# Power_Supply.net
KiCad netlist of a schematic drawn in Altium Designer
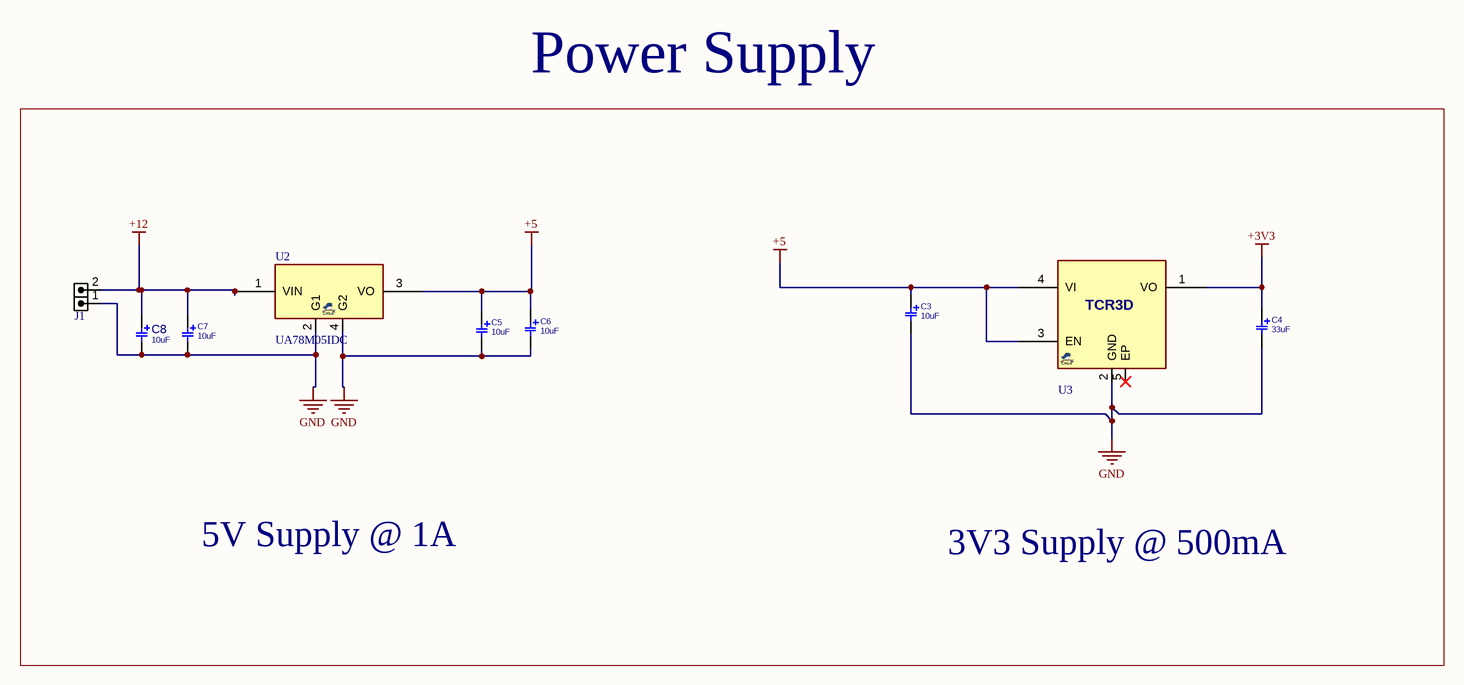
[diagram p0: Power_Supply.SchDoc]

(export (version "E")
  (design (tool "Eeschema 10.0.6"))
  (components
    (comp (ref "C3")
      (value "10uF")
      (footprint "C_TN_3216")
      (description "CAP, SMD, TAN,")
      (libsource (lib "passive_smd") (part "CAP_SMD_TAN_3216"))
    )
    (comp (ref "C4")
      (value "33uF")
      (footprint "C_TN_3216")
      (description "CAP, SMD, TAN,")
      (libsource (lib "passive_smd") (part "CAP_SMD_TAN_3216"))
    )
    (comp (ref "C5")
      (value "10uF")
      (footprint "C_TN_3216")
      (description "CAP, SMD, TAN,")
      (libsource (lib "passive_smd") (part "CAP_SMD_TAN_3216"))
    )
    (comp (ref "C6")
      (value "10uF")
      (footprint "C_TN_3216")
      (description "CAP, SMD, TAN,")
      (libsource (lib "passive_smd") (part "CAP_SMD_TAN_3216"))
    )
    (comp (ref "C7")
      (value "10uF")
      (footprint "C_TN_3216")
      (description "CAP, SMD, TAN,")
      (libsource (lib "passive_smd") (part "CAP_SMD_TAN_3216"))
    )
    (comp (ref "C8")
      (value "10uF")
      (footprint "C_EL_8")
      (description "CAP, THD, ELEC,")
      (fields (field (name "MANF_P#") "MANF_PART#") (field (name "MANF") "MANF"))
      (libsource (lib "passive_smd") (part "CAP_SMD_EL"))
    )
    (comp (ref "J1")
      (value "HDRM2")
      (footprint "HDR_M_1X2")
      (description "CONN, HEADER, Male, pitch: 2.54mm, 2POS")
      (libsource (lib "conn_header_2.54_st") (part "HDR_M_1X2"))
    )
    (comp (ref "U2")
      (value "UA78M05IDC")
      (footprint "SOT223_4")
      (description "REG, Linear, Fixed, 5v, 0.5A, SOT-223")
      (fields (field (name "MANF_P#") "UA78M05IDCYR") (field (name "MANF") "TI"))
      (libsource (lib "pwr_reg_linear_78xx79xx") (part "VREG_78M05_SOT223"))
    )
    (comp (ref "U3")
      (value "TCR3D")
      (footprint "SON65_4T_1010")
      (description "REG, Linear, LDO0.3V, Fixed, 300mA, VIN2~5.25V, VOUT1~4.5V,DFN4 1X1mm")
      (fields
        (field (name "MANF") "TOSHIBA")
        (field (name "MANF_P#") "TCR3DM10, TCR3DM105, TCR3DM12, TCR3DM15, TCR3DM18, TCR3DM25, TCR3DM33")
      )
      (libsource (lib "pwr_reg_linear_LDO_highPSRR") (part "VREG_TCR3D_DFN4"))
    )
  )
  (nets
    (net (code "1") (name "+3V3") (class "Default")
      (node (ref "C4") (pin "1") (pinfunction "1_1") (pintype "passive"))
      (node (ref "U3") (pin "1") (pinfunction "VO_1") (pintype "passive"))
    )
    (net (code "2") (name "+5") (class "Default")
      (node (ref "C3") (pin "1") (pinfunction "1_1") (pintype "passive"))
      (node (ref "C5") (pin "1") (pinfunction "1_1") (pintype "passive"))
      (node (ref "C6") (pin "1") (pinfunction "1_1") (pintype "passive"))
      (node (ref "U2") (pin "3") (pinfunction "VO_3") (pintype "passive"))
      (node (ref "U3") (pin "3") (pinfunction "EN_3") (pintype "passive"))
      (node (ref "U3") (pin "4") (pinfunction "VI_4") (pintype "passive"))
    )
    (net (code "3") (name "+12") (class "Default")
      (node (ref "C7") (pin "1") (pinfunction "1_1") (pintype "passive"))
      (node (ref "C8") (pin "1") (pinfunction "1_1") (pintype "passive"))
      (node (ref "J1") (pin "2") (pinfunction "2_2") (pintype "passive"))
      (node (ref "U2") (pin "1") (pinfunction "VIN_1") (pintype "passive"))
    )
    (net (code "4") (name "GND") (class "Default")
      (node (ref "C3") (pin "2") (pinfunction "2_2") (pintype "passive"))
      (node (ref "C4") (pin "2") (pinfunction "2_2") (pintype "passive"))
      (node (ref "C5") (pin "2") (pinfunction "2_2") (pintype "passive"))
      (node (ref "C6") (pin "2") (pinfunction "2_2") (pintype "passive"))
      (node (ref "C7") (pin "2") (pinfunction "2_2") (pintype "passive"))
      (node (ref "C8") (pin "2") (pinfunction "2_2") (pintype "passive"))
      (node (ref "J1") (pin "1") (pinfunction "1_1") (pintype "passive"))
      (node (ref "U2") (pin "2") (pinfunction "G1_2") (pintype "passive"))
      (node (ref "U2") (pin "4") (pinfunction "G2_4") (pintype "passive"))
      (node (ref "U3") (pin "2") (pinfunction "GND_2") (pintype "passive"))
    )
    (net (code "5") (name "unconnected-(U3-EP-Pad5)") (class "Default")
      (node (ref "U3") (pin "5") (pinfunction "EP_5") (pintype "passive+no_connect"))
    )
  )
)
